# esp32__EasyEDA_file.net
KiCad netlist of a schematic drawn in EasyEDA
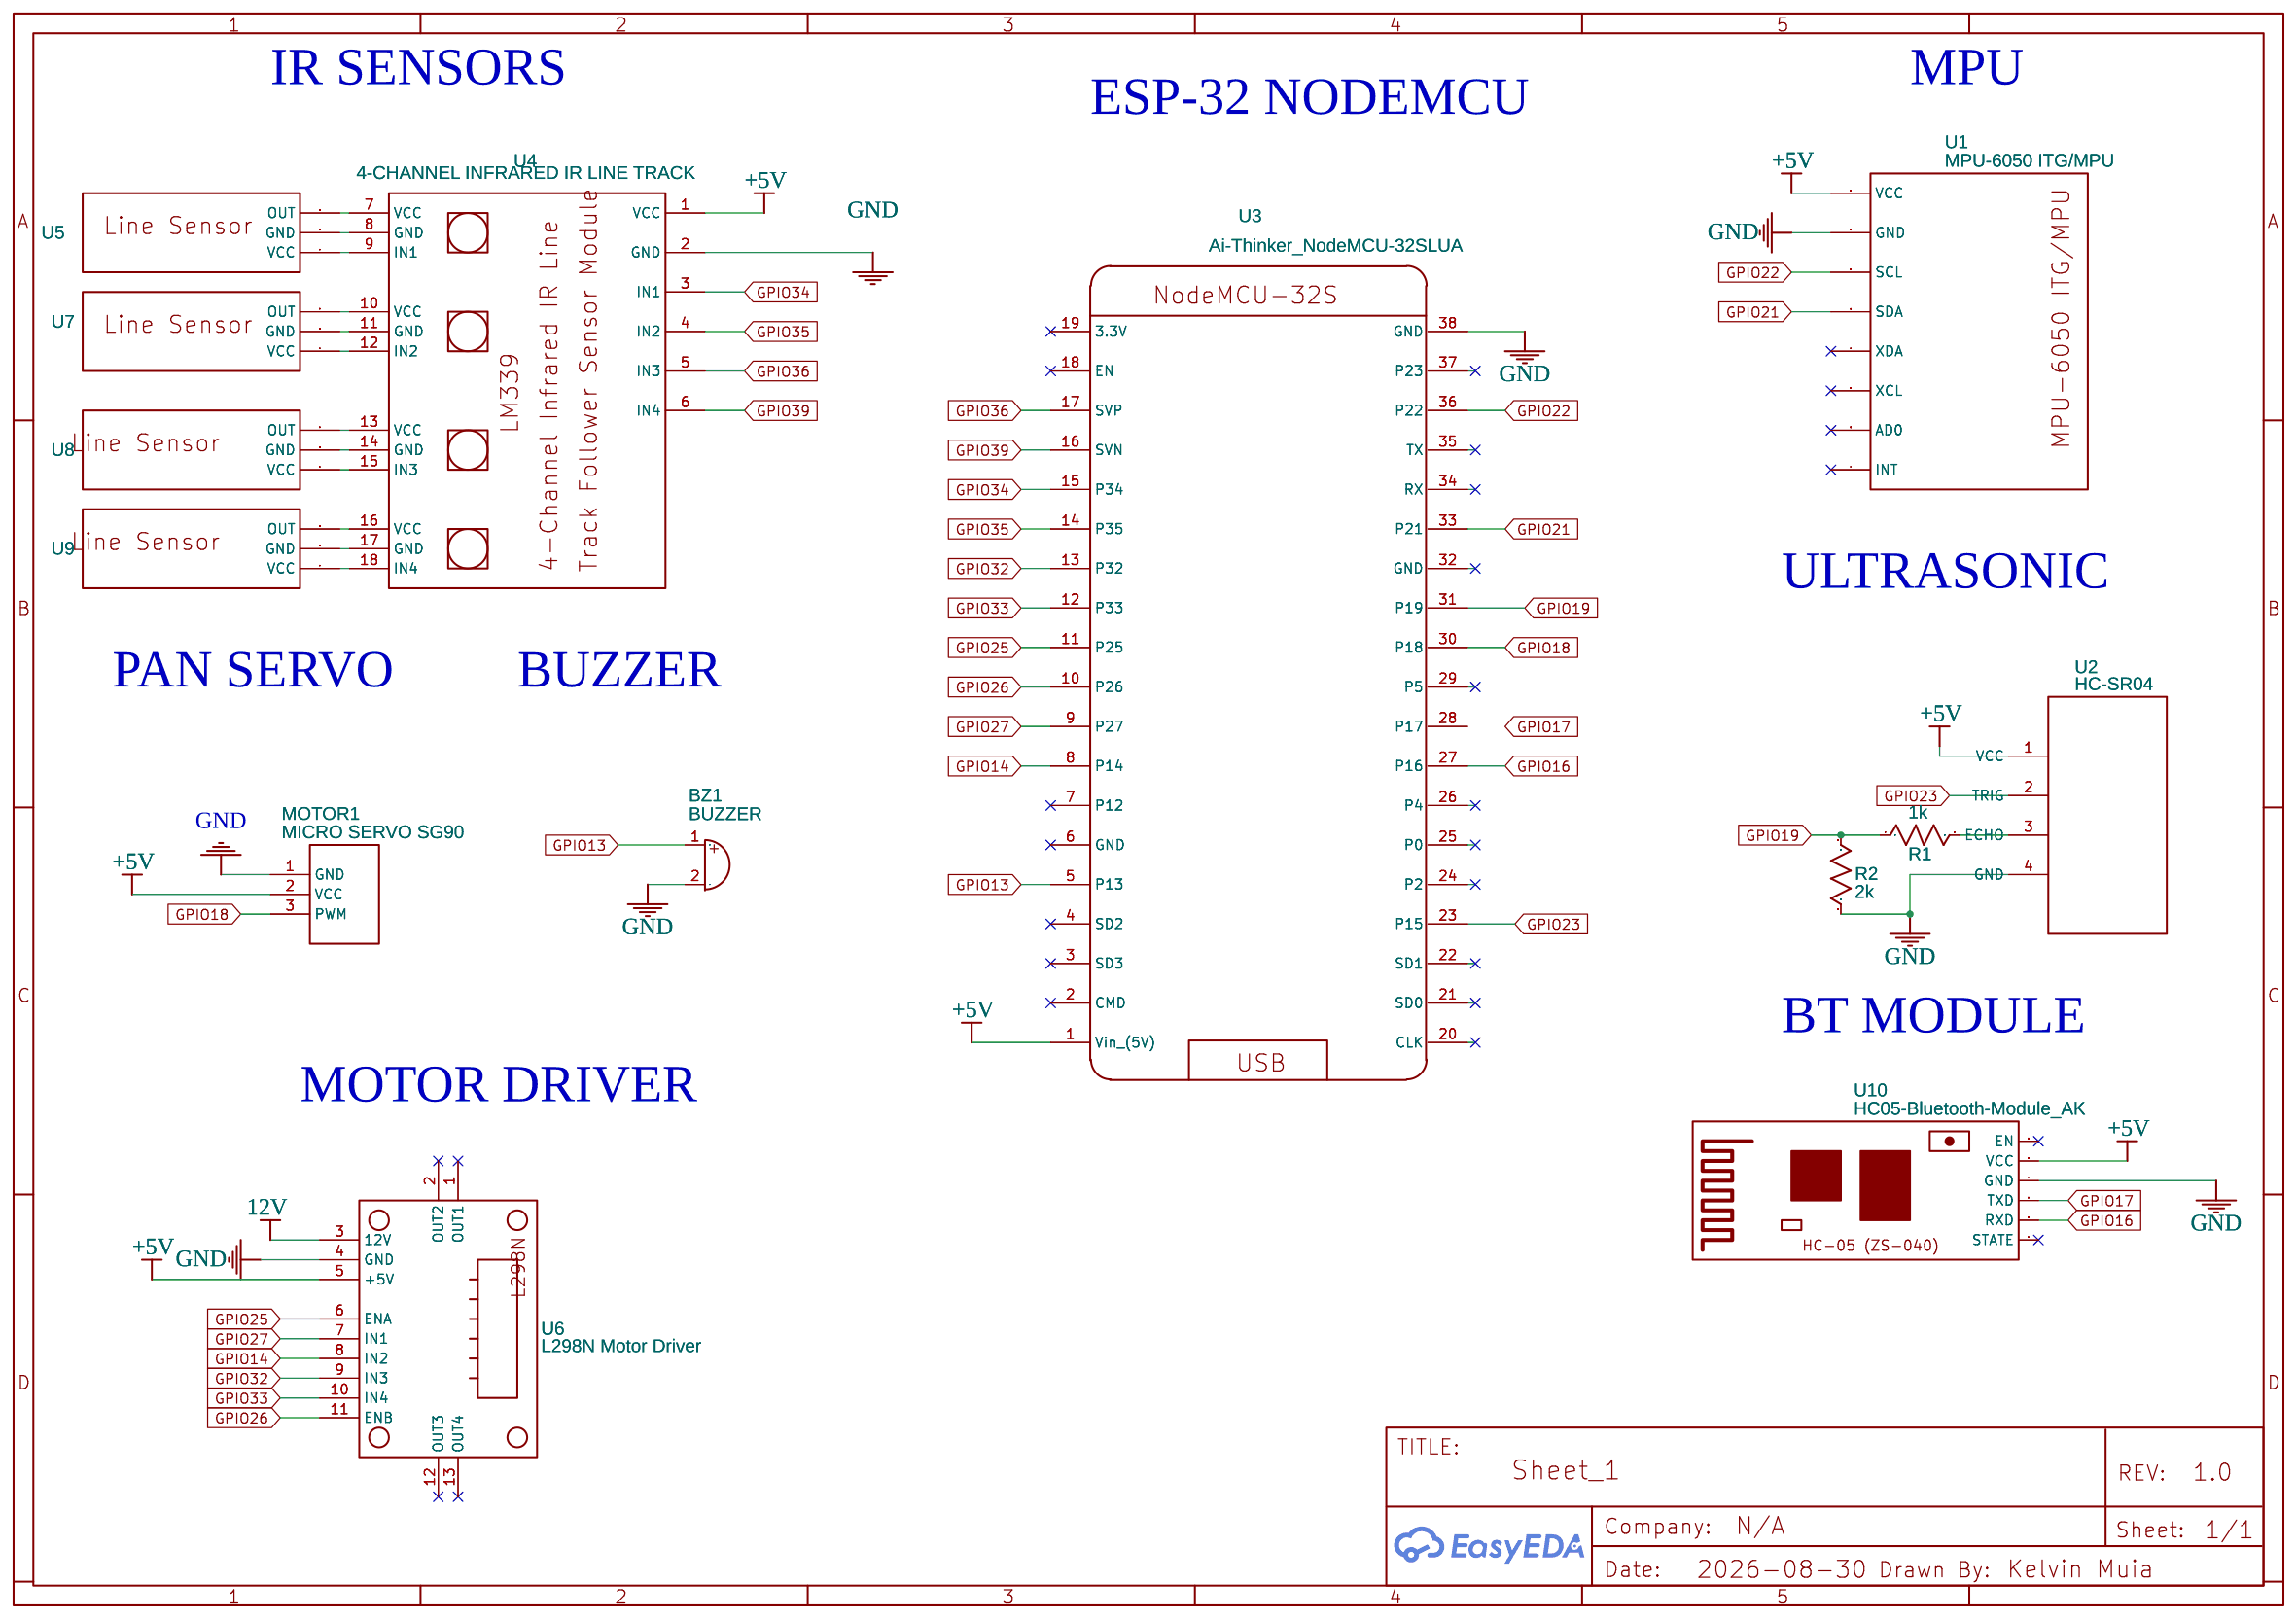
[diagram p0: schematic sheet]

(export (version "E")
  (design (tool "Eeschema 10.0.6"))
  (components
    (comp (ref "BZ1") (value "BUZZER") (libsource (lib "") (part "Device_Buzzer")))
    (comp (ref "MOTOR1") (value "MICRO SERVO SG90") (libsource (lib "") (part "MICRO SERVO SG90")))
    (comp (ref "R1") (value "1k") (libsource (lib "") (part "R_0603_US_1")))
    (comp (ref "R2") (value "2k") (libsource (lib "") (part "R_0603_US")))
    (comp (ref "U1") (value "MPU-6050 ITG/MPU") (libsource (lib "") (part "MPU-6050 ITG/MPU")))
    (comp (ref "U2") (value "HC-SR04") (libsource (lib "") (part "HC-SR04")))
    (comp (ref "U3")
      (value "Ai-Thinker_NodeMCU-32SLUA")
      (fields (field (name "Manufacturer Part") "NodeMCU-32SLua") (field (name "Manufacturer") "Ai-Thinker"))
      (libsource (lib "") (part "Ai-Thinker_NodeMCU-32SLUA"))
    )
    (comp (ref "U4")
      (value "4-CHANNEL INFRARED IR LINE TRACK")
      (fields (field (name "Manufacturer Part") "LM339"))
      (libsource (lib "") (part "4-CHANNEL INFRARED IR LINE TRACK FOLLOWER SENSOR MODULE (LM339) COPY"))
    )
    (comp (ref "U5")
      (value "MH-Sensor-Series Line Sensor")
      (libsource (lib "") (part "MH-Sensor-Series Line Sensor_1"))
    )
    (comp (ref "U6") (value "L298N Motor Driver") (libsource (lib "") (part "L298N Motor Driver")))
    (comp (ref "U7")
      (value "MH-Sensor-Series Line Sensor")
      (libsource (lib "") (part "MH-Sensor-Series Line Sensor_1"))
    )
    (comp (ref "U8")
      (value "MH-Sensor-Series Line Sensor")
      (libsource (lib "") (part "MH-Sensor-Series Line Sensor"))
    )
    (comp (ref "U9")
      (value "MH-Sensor-Series Line Sensor")
      (libsource (lib "") (part "MH-Sensor-Series Line Sensor"))
    )
    (comp (ref "U10")
      (value "HC05-Bluetooth-Module_AK")
      (libsource (lib "") (part "HC05-Bluetooth-Module_AK"))
    )
  )
  (nets
    (net (code "1") (name "+5V") (class "Default")
      (node (ref "MOTOR1") (pin "2") (pinfunction "VCC_2") (pintype "unspecified"))
      (node (ref "U1") (pin "0") (pinfunction "VCC_0") (pintype "unspecified"))
      (node (ref "U10") (pin "5") (pinfunction "VCC_5") (pintype "output"))
      (node (ref "U3") (pin "1") (pinfunction "Vin_(5V)_1") (pintype "unspecified"))
      (node (ref "U4") (pin "1") (pinfunction "VCC_1") (pintype "unspecified"))
      (node (ref "U6") (pin "5") (pinfunction "+5V_5") (pintype "unspecified"))
    )
    (net (code "2") (name "12V") (class "Default")
      (node (ref "U6") (pin "3") (pinfunction "12V_3") (pintype "unspecified"))
    )
    (net (code "3") (name "GND") (class "Default")
      (node (ref "BZ1") (pin "2") (pinfunction "-_2") (pintype "unspecified"))
      (node (ref "MOTOR1") (pin "1") (pinfunction "GND_1") (pintype "unspecified"))
      (node (ref "R2") (pin "2") (pinfunction "2_2") (pintype "unspecified"))
      (node (ref "U1") (pin "1") (pinfunction "GND_1") (pintype "unspecified"))
      (node (ref "U10") (pin "4") (pinfunction "GND_4") (pintype "input"))
      (node (ref "U3") (pin "38") (pinfunction "GND_38") (pintype "unspecified"))
      (node (ref "U4") (pin "2") (pinfunction "GND_2") (pintype "unspecified"))
      (node (ref "U6") (pin "4") (pinfunction "GND_4") (pintype "unspecified"))
    )
    (net (code "4") (name "GPIO13") (class "Default")
      (node (ref "BZ1") (pin "1") (pinfunction "+_1") (pintype "unspecified"))
      (node (ref "U3") (pin "5") (pinfunction "P13_5") (pintype "unspecified"))
    )
    (net (code "5") (name "GPIO14") (class "Default")
      (node (ref "U3") (pin "8") (pinfunction "P14_8") (pintype "unspecified"))
      (node (ref "U6") (pin "8") (pinfunction "IN2_8") (pintype "unspecified"))
    )
    (net (code "6") (name "GPIO16") (class "Default")
      (node (ref "U10") (pin "2") (pinfunction "RXD_2") (pintype "passive"))
      (node (ref "U3") (pin "27") (pinfunction "P16_27") (pintype "unspecified"))
    )
    (net (code "7") (name "GPIO17") (class "Default")
      (node (ref "U10") (pin "3") (pinfunction "TXD_3") (pintype "passive"))
    )
    (net (code "8") (name "GPIO18") (class "Default")
      (node (ref "MOTOR1") (pin "3") (pinfunction "PWM_3") (pintype "unspecified"))
      (node (ref "U3") (pin "30") (pinfunction "P18_30") (pintype "unspecified"))
    )
    (net (code "9") (name "GPIO19") (class "Default")
      (node (ref "R1") (pin "1") (pinfunction "1_1") (pintype "unspecified"))
      (node (ref "R2") (pin "1") (pinfunction "1_1") (pintype "unspecified"))
      (node (ref "U3") (pin "31") (pinfunction "P19_31") (pintype "unspecified"))
    )
    (net (code "10") (name "GPIO21") (class "Default")
      (node (ref "U1") (pin "3") (pinfunction "SDA_3") (pintype "unspecified"))
      (node (ref "U3") (pin "33") (pinfunction "P21_33") (pintype "unspecified"))
    )
    (net (code "11") (name "GPIO22") (class "Default")
      (node (ref "U1") (pin "2") (pinfunction "SCL_2") (pintype "unspecified"))
      (node (ref "U3") (pin "36") (pinfunction "P22_36") (pintype "unspecified"))
    )
    (net (code "12") (name "GPIO23") (class "Default")
      (node (ref "U3") (pin "23") (pinfunction "P15_23") (pintype "unspecified"))
    )
    (net (code "13") (name "GPIO25") (class "Default")
      (node (ref "U3") (pin "11") (pinfunction "P25_11") (pintype "unspecified"))
      (node (ref "U6") (pin "6") (pinfunction "ENA_6") (pintype "unspecified"))
    )
    (net (code "14") (name "GPIO26") (class "Default")
      (node (ref "U3") (pin "10") (pinfunction "P26_10") (pintype "unspecified"))
      (node (ref "U6") (pin "11") (pinfunction "ENB_11") (pintype "unspecified"))
    )
    (net (code "15") (name "GPIO27") (class "Default")
      (node (ref "U3") (pin "9") (pinfunction "P27_9") (pintype "unspecified"))
      (node (ref "U6") (pin "7") (pinfunction "IN1_7") (pintype "unspecified"))
    )
    (net (code "16") (name "GPIO32") (class "Default")
      (node (ref "U3") (pin "13") (pinfunction "P32_13") (pintype "unspecified"))
      (node (ref "U6") (pin "9") (pinfunction "IN3_9") (pintype "unspecified"))
    )
    (net (code "17") (name "GPIO33") (class "Default")
      (node (ref "U3") (pin "12") (pinfunction "P33_12") (pintype "unspecified"))
      (node (ref "U6") (pin "10") (pinfunction "IN4_10") (pintype "unspecified"))
    )
    (net (code "18") (name "GPIO34") (class "Default")
      (node (ref "U3") (pin "15") (pinfunction "P34_15") (pintype "unspecified"))
      (node (ref "U4") (pin "3") (pinfunction "IN1_3") (pintype "unspecified"))
    )
    (net (code "19") (name "GPIO35") (class "Default")
      (node (ref "U3") (pin "14") (pinfunction "P35_14") (pintype "unspecified"))
      (node (ref "U4") (pin "4") (pinfunction "IN2_4") (pintype "unspecified"))
    )
    (net (code "20") (name "GPIO36") (class "Default")
      (node (ref "U3") (pin "17") (pinfunction "SVP_17") (pintype "unspecified"))
      (node (ref "U4") (pin "5") (pinfunction "IN3_5") (pintype "unspecified"))
    )
    (net (code "21") (name "GPIO39") (class "Default")
      (node (ref "U3") (pin "16") (pinfunction "SVN_16") (pintype "unspecified"))
      (node (ref "U4") (pin "6") (pinfunction "IN4_6") (pintype "unspecified"))
    )
    (net (code "22") (name "Net-(U5-GND)") (class "Default")
      (node (ref "U4") (pin "8") (pinfunction "GND_8") (pintype "unspecified"))
      (node (ref "U5") (pin "3") (pinfunction "GND_3") (pintype "passive"))
    )
    (net (code "23") (name "Net-(U5-OUT)") (class "Default")
      (node (ref "U4") (pin "7") (pinfunction "VCC_7") (pintype "unspecified"))
      (node (ref "U5") (pin "2") (pinfunction "OUT_2") (pintype "unspecified"))
    )
    (net (code "24") (name "Net-(U5-VCC)") (class "Default")
      (node (ref "U4") (pin "9") (pinfunction "IN1_9") (pintype "unspecified"))
      (node (ref "U5") (pin "4") (pinfunction "VCC_4") (pintype "passive"))
    )
    (net (code "25") (name "Net-(U7-GND)") (class "Default")
      (node (ref "U4") (pin "11") (pinfunction "GND_11") (pintype "unspecified"))
      (node (ref "U7") (pin "3") (pinfunction "GND_3") (pintype "passive"))
    )
    (net (code "26") (name "Net-(U7-OUT)") (class "Default")
      (node (ref "U4") (pin "10") (pinfunction "VCC_10") (pintype "unspecified"))
      (node (ref "U7") (pin "2") (pinfunction "OUT_2") (pintype "unspecified"))
    )
    (net (code "27") (name "Net-(U7-VCC)") (class "Default")
      (node (ref "U4") (pin "12") (pinfunction "IN2_12") (pintype "unspecified"))
      (node (ref "U7") (pin "4") (pinfunction "VCC_4") (pintype "passive"))
    )
    (net (code "28") (name "Net-(U8-GND)") (class "Default")
      (node (ref "U4") (pin "14") (pinfunction "GND_14") (pintype "unspecified"))
      (node (ref "U8") (pin "3") (pinfunction "GND_3") (pintype "passive"))
    )
    (net (code "29") (name "Net-(U8-OUT)") (class "Default")
      (node (ref "U4") (pin "13") (pinfunction "VCC_13") (pintype "unspecified"))
      (node (ref "U8") (pin "2") (pinfunction "OUT_2") (pintype "unspecified"))
    )
    (net (code "30") (name "Net-(U8-VCC)") (class "Default")
      (node (ref "U4") (pin "15") (pinfunction "IN3_15") (pintype "unspecified"))
      (node (ref "U8") (pin "4") (pinfunction "VCC_4") (pintype "passive"))
    )
    (net (code "31") (name "Net-(U9-GND)") (class "Default")
      (node (ref "U4") (pin "17") (pinfunction "GND_17") (pintype "unspecified"))
      (node (ref "U9") (pin "3") (pinfunction "GND_3") (pintype "passive"))
    )
    (net (code "32") (name "Net-(U9-OUT)") (class "Default")
      (node (ref "U4") (pin "16") (pinfunction "VCC_16") (pintype "unspecified"))
      (node (ref "U9") (pin "2") (pinfunction "OUT_2") (pintype "unspecified"))
    )
    (net (code "33") (name "Net-(U9-VCC)") (class "Default")
      (node (ref "U4") (pin "18") (pinfunction "IN4_18") (pintype "unspecified"))
      (node (ref "U9") (pin "4") (pinfunction "VCC_4") (pintype "passive"))
    )
    (net (code "34") (name "unconnected-(R1-Pad2)") (class "Default")
      (node (ref "R1") (pin "2") (pinfunction "2_2") (pintype "unspecified"))
    )
    (net (code "35") (name "unconnected-(U1-AD0-Pad6)") (class "Default")
      (node (ref "U1") (pin "6") (pinfunction "AD0_6") (pintype "unspecified+no_connect"))
    )
    (net (code "36") (name "unconnected-(U1-INT-Pad7)") (class "Default")
      (node (ref "U1") (pin "7") (pinfunction "INT_7") (pintype "unspecified+no_connect"))
    )
    (net (code "37") (name "unconnected-(U1-XCL-Pad5)") (class "Default")
      (node (ref "U1") (pin "5") (pinfunction "XCL_5") (pintype "unspecified+no_connect"))
    )
    (net (code "38") (name "unconnected-(U1-XDA-Pad4)") (class "Default")
      (node (ref "U1") (pin "4") (pinfunction "XDA_4") (pintype "unspecified+no_connect"))
    )
    (net (code "39") (name "unconnected-(U2-ECHO-Pad3)") (class "Default")
      (node (ref "U2") (pin "3") (pinfunction "ECHO_3") (pintype "unspecified"))
    )
    (net (code "40") (name "unconnected-(U2-GND-Pad4)") (class "Default")
      (node (ref "U2") (pin "4") (pinfunction "GND_4") (pintype "unspecified"))
    )
    (net (code "41") (name "unconnected-(U2-TRIG-Pad2)") (class "Default")
      (node (ref "U2") (pin "2") (pinfunction "TRIG_2") (pintype "unspecified"))
    )
    (net (code "42") (name "unconnected-(U2-VCC-Pad1)") (class "Default")
      (node (ref "U2") (pin "1") (pinfunction "VCC_1") (pintype "unspecified"))
    )
    (net (code "43") (name "unconnected-(U3-3.3V-Pad19)") (class "Default")
      (node (ref "U3") (pin "19") (pinfunction "3.3V_19") (pintype "unspecified+no_connect"))
    )
    (net (code "44") (name "unconnected-(U3-CLK-Pad20)") (class "Default")
      (node (ref "U3") (pin "20") (pinfunction "CLK_20") (pintype "unspecified+no_connect"))
    )
    (net (code "45") (name "unconnected-(U3-CMD-Pad2)") (class "Default")
      (node (ref "U3") (pin "2") (pinfunction "CMD_2") (pintype "unspecified+no_connect"))
    )
    (net (code "46") (name "unconnected-(U3-EN-Pad18)") (class "Default")
      (node (ref "U3") (pin "18") (pinfunction "EN_18") (pintype "unspecified+no_connect"))
    )
    (net (code "47") (name "unconnected-(U3-GND-Pad6)") (class "Default")
      (node (ref "U3") (pin "6") (pinfunction "GND_6") (pintype "unspecified+no_connect"))
    )
    (net (code "48") (name "unconnected-(U3-GND-Pad32)") (class "Default")
      (node (ref "U3") (pin "32") (pinfunction "GND_32") (pintype "unspecified+no_connect"))
    )
    (net (code "49") (name "unconnected-(U3-P0-Pad25)") (class "Default")
      (node (ref "U3") (pin "25") (pinfunction "P0_25") (pintype "unspecified+no_connect"))
    )
    (net (code "50") (name "unconnected-(U3-P2-Pad24)") (class "Default")
      (node (ref "U3") (pin "24") (pinfunction "P2_24") (pintype "unspecified+no_connect"))
    )
    (net (code "51") (name "unconnected-(U3-P4-Pad26)") (class "Default")
      (node (ref "U3") (pin "26") (pinfunction "P4_26") (pintype "unspecified+no_connect"))
    )
    (net (code "52") (name "unconnected-(U3-P5-Pad29)") (class "Default")
      (node (ref "U3") (pin "29") (pinfunction "P5_29") (pintype "unspecified+no_connect"))
    )
    (net (code "53") (name "unconnected-(U3-P12-Pad7)") (class "Default")
      (node (ref "U3") (pin "7") (pinfunction "P12_7") (pintype "unspecified+no_connect"))
    )
    (net (code "54") (name "unconnected-(U3-P17-Pad28)") (class "Default")
      (node (ref "U3") (pin "28") (pinfunction "P17_28") (pintype "unspecified"))
    )
    (net (code "55") (name "unconnected-(U3-P23-Pad37)") (class "Default")
      (node (ref "U3") (pin "37") (pinfunction "P23_37") (pintype "unspecified+no_connect"))
    )
    (net (code "56") (name "unconnected-(U3-RX-Pad34)") (class "Default")
      (node (ref "U3") (pin "34") (pinfunction "RX_34") (pintype "unspecified+no_connect"))
    )
    (net (code "57") (name "unconnected-(U3-SD0-Pad21)") (class "Default")
      (node (ref "U3") (pin "21") (pinfunction "SD0_21") (pintype "unspecified+no_connect"))
    )
    (net (code "58") (name "unconnected-(U3-SD1-Pad22)") (class "Default")
      (node (ref "U3") (pin "22") (pinfunction "SD1_22") (pintype "unspecified+no_connect"))
    )
    (net (code "59") (name "unconnected-(U3-SD2-Pad4)") (class "Default")
      (node (ref "U3") (pin "4") (pinfunction "SD2_4") (pintype "unspecified+no_connect"))
    )
    (net (code "60") (name "unconnected-(U3-SD3-Pad3)") (class "Default")
      (node (ref "U3") (pin "3") (pinfunction "SD3_3") (pintype "unspecified+no_connect"))
    )
    (net (code "61") (name "unconnected-(U3-TX-Pad35)") (class "Default")
      (node (ref "U3") (pin "35") (pinfunction "TX_35") (pintype "unspecified+no_connect"))
    )
    (net (code "62") (name "unconnected-(U6-OUT1-Pad1)") (class "Default")
      (node (ref "U6") (pin "1") (pinfunction "OUT1_1") (pintype "unspecified+no_connect"))
    )
    (net (code "63") (name "unconnected-(U6-OUT2-Pad2)") (class "Default")
      (node (ref "U6") (pin "2") (pinfunction "OUT2_2") (pintype "unspecified+no_connect"))
    )
    (net (code "64") (name "unconnected-(U6-OUT3-Pad12)") (class "Default")
      (node (ref "U6") (pin "12") (pinfunction "OUT3_12") (pintype "unspecified+no_connect"))
    )
    (net (code "65") (name "unconnected-(U6-OUT4-Pad13)") (class "Default")
      (node (ref "U6") (pin "13") (pinfunction "OUT4_13") (pintype "unspecified+no_connect"))
    )
    (net (code "66") (name "unconnected-(U10-EN-Pad6)") (class "Default")
      (node (ref "U10") (pin "6") (pinfunction "EN_6") (pintype "bidirectional+no_connect"))
    )
    (net (code "67") (name "unconnected-(U10-STATE-Pad1)") (class "Default")
      (node (ref "U10") (pin "1") (pinfunction "STATE_1") (pintype "passive+no_connect"))
    )
  )
)
